# Driver_Channel_DRV8825.net
KiCad netlist of a schematic drawn in Altium Designer
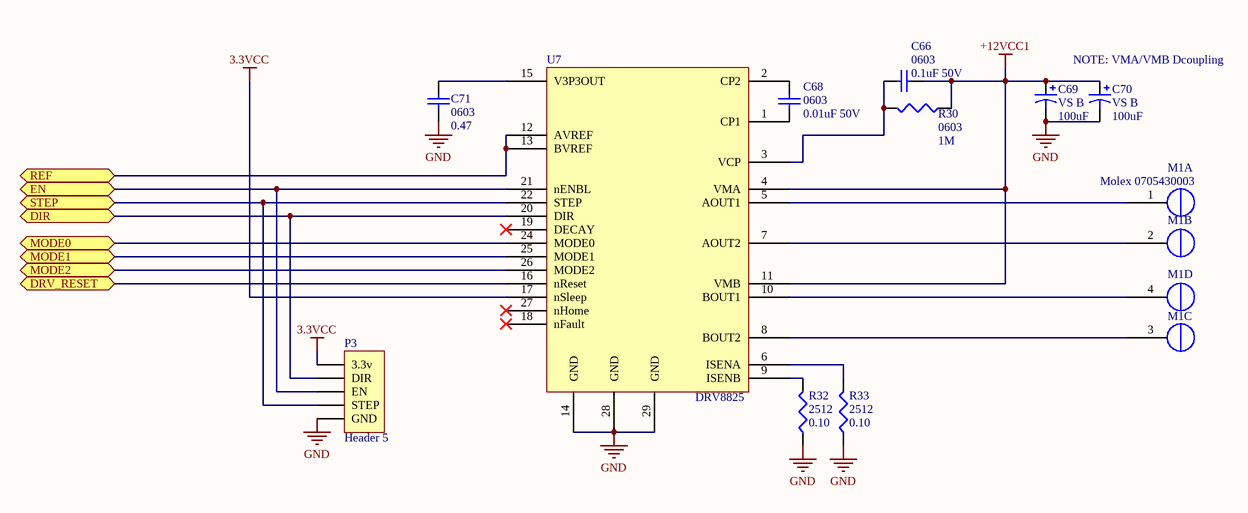
[diagram p0: Driver Channel DRV8825.SchDoc]

(export (version "E")
  (design (tool "Eeschema 10.0.6"))
  (components
    (comp (ref "C66")
      (value "0603")
      (footprint "1608[0603]")
      (description "Capacitor (Semiconductor SIM Model)")
      (fields (field (name "ALTIUM_VALUE") "0.1uF 50V") (field (name "PUBLISHER") "Altium Limited"))
      (libsource (lib "Miscellaneous Devices") (part "Cap Semi"))
    )
    (comp (ref "C68")
      (value "0603")
      (footprint "1608[0603]")
      (description "Capacitor (Semiconductor SIM Model)")
      (fields (field (name "ALTIUM_VALUE") "0.01uF 50V") (field (name "PUBLISHER") "Altium Limited"))
      (libsource (lib "Miscellaneous Devices") (part "Cap Semi"))
    )
    (comp (ref "C69")
      (value "VS B")
      (footprint "Panasonic VS B")
      (description "Polarized Capacitor (Radial)")
      (fields (field (name "ALTIUM_VALUE") "100uF") (field (name "PUBLISHER") "Altium Limited"))
      (libsource (lib "Miscellaneous Devices") (part "Cap Pol1"))
    )
    (comp (ref "C70")
      (value "VS B")
      (footprint "Panasonic VS B")
      (description "Polarized Capacitor (Radial)")
      (fields (field (name "ALTIUM_VALUE") "100uF") (field (name "PUBLISHER") "Altium Limited"))
      (libsource (lib "Miscellaneous Devices") (part "Cap Pol1"))
    )
    (comp (ref "C71")
      (value "0603")
      (footprint "1608[0603]")
      (description "Capacitor (Semiconductor SIM Model)")
      (fields (field (name "ALTIUM_VALUE") "0.47") (field (name "PUBLISHER") "Altium Limited"))
      (libsource (lib "Miscellaneous Devices") (part "Cap Semi"))
    )
    (comp (ref "M1")
      (value "Molex 0705430003")
      (footprint "4POL254")
      (description "Molex 4 Pin Clip Connector")
      (libsource (lib "ZMBo Schematic Library") (part "Molex 0705430003 Alt"))
    )
    (comp (ref "P3")
      (value "Header 5")
      (footprint "HDR1X5")
      (description "Header, 5-Pin")
      (fields (field (name "PUBLISHER") "Altium Limited"))
      (libsource (lib "Miscellaneous Connectors") (part "Header 5"))
    )
    (comp (ref "R30")
      (value "0603")
      (footprint "J1-0603")
      (description "Resistor")
      (fields (field (name "ALTIUM_VALUE") "1M") (field (name "PUBLISHER") "Altium Limited"))
      (libsource (lib "Miscellaneous Devices") (part "Res3"))
    )
    (comp (ref "R32")
      (value "2512")
      (footprint "Resistor2512")
      (description "Resistor")
      (fields (field (name "ALTIUM_VALUE") "0.10") (field (name "PUBLISHER") "Altium Limited"))
      (libsource (lib "Miscellaneous Devices") (part "Res3"))
    )
    (comp (ref "R33")
      (value "2512")
      (footprint "Resistor2512")
      (description "Resistor")
      (fields (field (name "ALTIUM_VALUE") "0.10") (field (name "PUBLISHER") "Altium Limited"))
      (libsource (lib "Miscellaneous Devices") (part "Res3"))
    )
    (comp (ref "U7")
      (value "DRV8825")
      (footprint "DRV8825")
      (description "DRV8825 Ti Stepper Driver")
      (libsource (lib "ZMBo Schematic Library") (part "DRV8825"))
    )
  )
  (nets
    (net (code "1") (name "+12VCC1") (class "Default")
      (node (ref "C66") (pin "1") (pinfunction "1_1") (pintype "passive"))
      (node (ref "C69") (pin "1") (pinfunction "1_1") (pintype "passive"))
      (node (ref "C70") (pin "1") (pinfunction "1_1") (pintype "passive"))
      (node (ref "R30") (pin "1") (pinfunction "1_1") (pintype "passive"))
      (node (ref "U7") (pin "11") (pinfunction "VMB_11") (pintype "passive"))
      (node (ref "U7") (pin "4") (pinfunction "VMA_4") (pintype "passive"))
    )
    (net (code "2") (name "/DIR") (class "Default")
      (node (ref "P3") (pin "2") (pinfunction "DIR_2") (pintype "passive"))
      (node (ref "U7") (pin "20") (pinfunction "DIR_20") (pintype "passive"))
    )
    (net (code "3") (name "/DRV_RESET") (class "Default")
      (node (ref "U7") (pin "16") (pinfunction "nReset_16") (pintype "passive"))
    )
    (net (code "4") (name "/EN") (class "Default")
      (node (ref "P3") (pin "3") (pinfunction "EN_3") (pintype "passive"))
      (node (ref "U7") (pin "21") (pinfunction "nENBL_21") (pintype "passive"))
    )
    (net (code "5") (name "/MODE0") (class "Default")
      (node (ref "U7") (pin "24") (pinfunction "MODE0_24") (pintype "passive"))
    )
    (net (code "6") (name "/MODE1") (class "Default")
      (node (ref "U7") (pin "25") (pinfunction "MODE1_25") (pintype "passive"))
    )
    (net (code "7") (name "/MODE2") (class "Default")
      (node (ref "U7") (pin "26") (pinfunction "MODE2_26") (pintype "passive"))
    )
    (net (code "8") (name "/REF") (class "Default")
      (node (ref "U7") (pin "12") (pinfunction "AVREF_12") (pintype "passive"))
      (node (ref "U7") (pin "13") (pinfunction "BVREF_13") (pintype "passive"))
    )
    (net (code "9") (name "/STEP") (class "Default")
      (node (ref "P3") (pin "4") (pinfunction "STEP_4") (pintype "passive"))
      (node (ref "U7") (pin "22") (pinfunction "STEP_22") (pintype "passive"))
    )
    (net (code "10") (name "3.3VCC") (class "Default")
      (node (ref "P3") (pin "1") (pinfunction "3.3v_1") (pintype "passive"))
      (node (ref "U7") (pin "17") (pinfunction "nSleep_17") (pintype "passive"))
    )
    (net (code "11") (name "GND") (class "Default")
      (node (ref "C69") (pin "2") (pinfunction "2_2") (pintype "passive"))
      (node (ref "C70") (pin "2") (pinfunction "2_2") (pintype "passive"))
      (node (ref "C71") (pin "1") (pinfunction "1_1") (pintype "passive"))
      (node (ref "P3") (pin "5") (pinfunction "GND_5") (pintype "passive"))
      (node (ref "R32") (pin "1") (pinfunction "1_1") (pintype "passive"))
      (node (ref "R33") (pin "1") (pinfunction "1_1") (pintype "passive"))
      (node (ref "U7") (pin "14") (pinfunction "GND_14") (pintype "passive"))
      (node (ref "U7") (pin "28") (pinfunction "GND_28") (pintype "passive"))
      (node (ref "U7") (pin "29") (pinfunction "GND_29") (pintype "passive"))
    )
    (net (code "12") (name "Net-(M1A-OUT2B)") (class "Default")
      (node (ref "M1") (pin "1") (pinfunction "OUT2B_1") (pintype "passive"))
      (node (ref "U7") (pin "5") (pinfunction "AOUT1_5") (pintype "passive"))
    )
    (net (code "13") (name "Net-(M1B-OUT2A)") (class "Default")
      (node (ref "M1") (pin "2") (pinfunction "OUT2A_2") (pintype "passive"))
      (node (ref "U7") (pin "7") (pinfunction "AOUT2_7") (pintype "passive"))
    )
    (net (code "14") (name "Net-(M1C-OUT1A)") (class "Default")
      (node (ref "M1") (pin "3") (pinfunction "OUT1A_3") (pintype "passive"))
      (node (ref "U7") (pin "8") (pinfunction "BOUT2_8") (pintype "passive"))
    )
    (net (code "15") (name "Net-(M1D-OUT1B)") (class "Default")
      (node (ref "M1") (pin "4") (pinfunction "OUT1B_4") (pintype "passive"))
      (node (ref "U7") (pin "10") (pinfunction "BOUT1_10") (pintype "passive"))
    )
    (net (code "16") (name "Net-(U7-CP1)") (class "Default")
      (node (ref "C68") (pin "1") (pinfunction "1_1") (pintype "passive"))
      (node (ref "U7") (pin "1") (pinfunction "CP1_1") (pintype "passive"))
    )
    (net (code "17") (name "Net-(U7-CP2)") (class "Default")
      (node (ref "C68") (pin "2") (pinfunction "2_2") (pintype "passive"))
      (node (ref "U7") (pin "2") (pinfunction "CP2_2") (pintype "passive"))
    )
    (net (code "18") (name "Net-(U7-ISENA)") (class "Default")
      (node (ref "R33") (pin "2") (pinfunction "2_2") (pintype "passive"))
      (node (ref "U7") (pin "6") (pinfunction "ISENA_6") (pintype "passive"))
    )
    (net (code "19") (name "Net-(U7-ISENB)") (class "Default")
      (node (ref "R32") (pin "2") (pinfunction "2_2") (pintype "passive"))
      (node (ref "U7") (pin "9") (pinfunction "ISENB_9") (pintype "passive"))
    )
    (net (code "20") (name "Net-(U7-V3P3OUT)") (class "Default")
      (node (ref "C71") (pin "2") (pinfunction "2_2") (pintype "passive"))
      (node (ref "U7") (pin "15") (pinfunction "V3P3OUT_15") (pintype "passive"))
    )
    (net (code "21") (name "Net-(U7-VCP)") (class "Default")
      (node (ref "C66") (pin "2") (pinfunction "2_2") (pintype "passive"))
      (node (ref "R30") (pin "2") (pinfunction "2_2") (pintype "passive"))
      (node (ref "U7") (pin "3") (pinfunction "VCP_3") (pintype "passive"))
    )
    (net (code "22") (name "unconnected-(U7-DECAY-Pad19)") (class "Default")
      (node (ref "U7") (pin "19") (pinfunction "DECAY_19") (pintype "passive+no_connect"))
    )
    (net (code "23") (name "unconnected-(U7-NC-Pad23)") (class "Default")
      (node (ref "U7") (pin "23") (pinfunction "NC_23") (pintype "passive"))
    )
    (net (code "24") (name "unconnected-(U7-nFault-Pad18)") (class "Default")
      (node (ref "U7") (pin "18") (pinfunction "nFault_18") (pintype "passive+no_connect"))
    )
    (net (code "25") (name "unconnected-(U7-nHome-Pad27)") (class "Default")
      (node (ref "U7") (pin "27") (pinfunction "nHome_27") (pintype "passive+no_connect"))
    )
  )
)
